# Banker_EDGE_2_SMA.net
KiCad netlist of a schematic drawn in Altium Designer
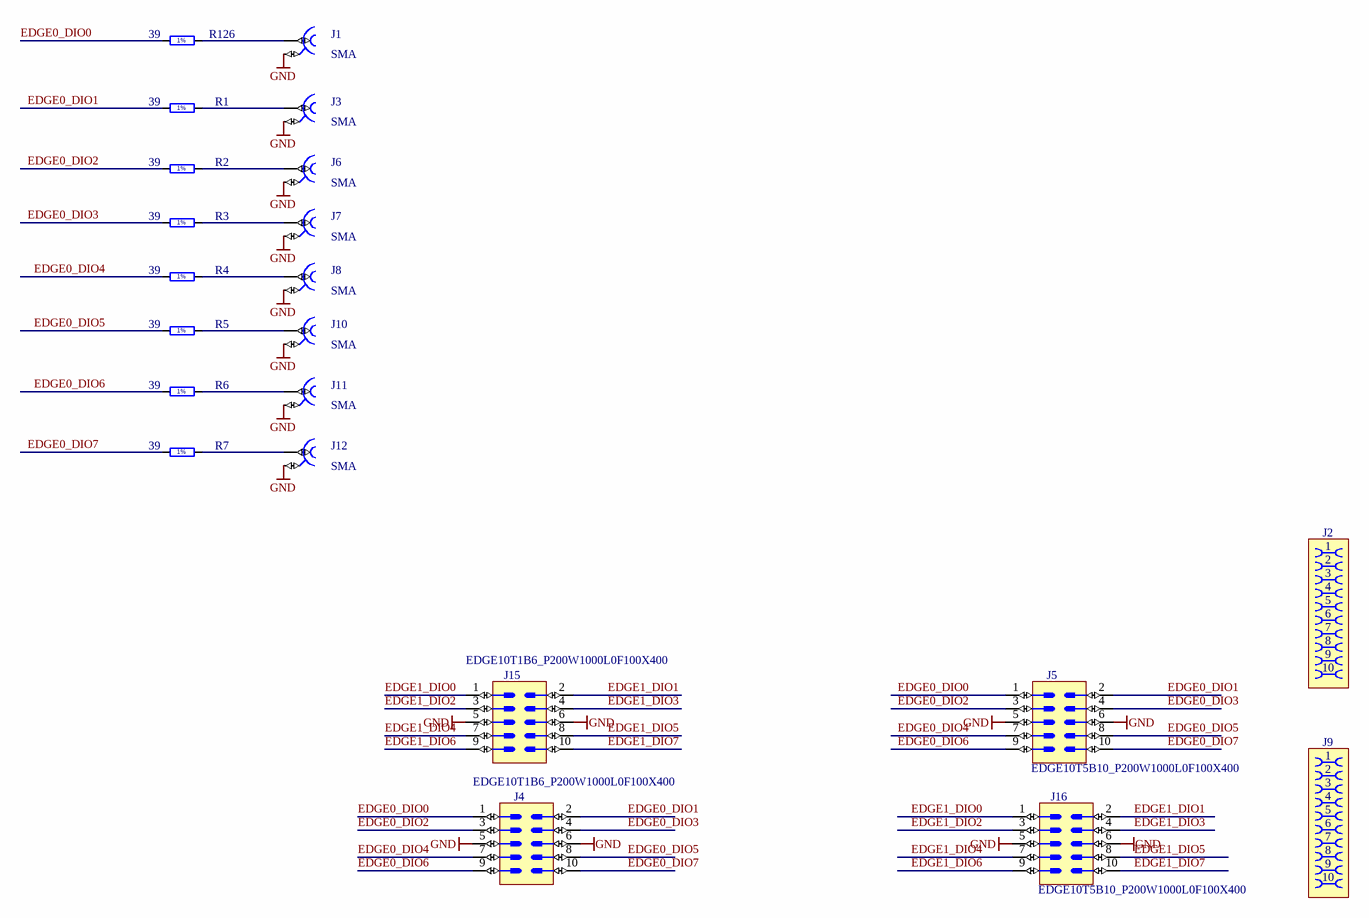
[diagram p0: Banker_EDGE_2_SMA.SchDoc]

(export (version "E")
  (design (tool "Eeschema 10.0.6"))
  (components
    (comp (ref "J1")
      (value "SMA")
      (footprint "Adam_TechRF2-19A-T-00-50-G")
      (description "SMA 50 Ohms Straight PCB Jack")
      (fields
        (field (name "PART NUMBER") "RF2-19A-T-00-50-G")
        (field (name "MANUFACTURER") "Adam Tech")
        (field (name "AUTHOR") "GK")
      )
      (libsource (lib "LIBRARY_SCH") (part "CON_SMA_V_AdamTech"))
    )
    (comp (ref "J2")
      (value "~")
      (footprint "AVX_00 9159 010 061 916")
      (description "Open Ended Card Edge Connector, 9159 Series")
      (fields
        (field (name "PART NUMBER") "AVX_00 9159 010 061 916")
        (field (name "MANUFACTURER") "AVX")
        (field (name "AUTHOR") "CERN DEM MR")
      )
      (libsource (lib "Connectors") (part "AVX_00 9159 010 061 916"))
    )
    (comp (ref "J3")
      (value "SMA")
      (footprint "Adam_TechRF2-19A-T-00-50-G")
      (description "SMA 50 Ohms Straight PCB Jack")
      (fields
        (field (name "PART NUMBER") "RF2-19A-T-00-50-G")
        (field (name "MANUFACTURER") "Adam Tech")
        (field (name "AUTHOR") "GK")
      )
      (libsource (lib "LIBRARY_SCH") (part "CON_SMA_V_AdamTech"))
    )
    (comp (ref "J4")
      (value "~")
      (footprint "EDGE10T1B6_P200W1000L0F100X400")
      (description "PCB Edge Connector 10 (2x5)")
      (fields
        (field (name "PART NUMBER") "EDGE10T1B6_P200W1000L0F100X400")
        (field (name "AUTHOR") "CERN DEM MR")
      )
      (libsource (lib "Connectors") (part "PCB Edge Connector 10 (2x5)"))
    )
    (comp (ref "J5")
      (value "~")
      (footprint "EDGE10T5B10_P200W1000L0F100X400")
      (description "PCB Edge Connector 10 (2x5)")
      (fields
        (field (name "PART NUMBER") "EDGE10T5B10_P200W1000L0F100X400")
        (field (name "AUTHOR") "CERN DEM MR")
      )
      (libsource (lib "Connectors") (part "PCB Edge Connector 10 (2x5)"))
    )
    (comp (ref "J6")
      (value "SMA")
      (footprint "Adam_TechRF2-19A-T-00-50-G")
      (description "SMA 50 Ohms Straight PCB Jack")
      (fields
        (field (name "PART NUMBER") "RF2-19A-T-00-50-G")
        (field (name "MANUFACTURER") "Adam Tech")
        (field (name "AUTHOR") "GK")
      )
      (libsource (lib "LIBRARY_SCH") (part "CON_SMA_V_AdamTech"))
    )
    (comp (ref "J7")
      (value "SMA")
      (footprint "Adam_TechRF2-19A-T-00-50-G")
      (description "SMA 50 Ohms Straight PCB Jack")
      (fields
        (field (name "PART NUMBER") "RF2-19A-T-00-50-G")
        (field (name "MANUFACTURER") "Adam Tech")
        (field (name "AUTHOR") "GK")
      )
      (libsource (lib "LIBRARY_SCH") (part "CON_SMA_V_AdamTech"))
    )
    (comp (ref "J8")
      (value "SMA")
      (footprint "Adam_TechRF2-19A-T-00-50-G")
      (description "SMA 50 Ohms Straight PCB Jack")
      (fields
        (field (name "PART NUMBER") "RF2-19A-T-00-50-G")
        (field (name "MANUFACTURER") "Adam Tech")
        (field (name "AUTHOR") "GK")
      )
      (libsource (lib "LIBRARY_SCH") (part "CON_SMA_V_AdamTech"))
    )
    (comp (ref "J9")
      (value "~")
      (footprint "AVX_00 9159 010 061 916")
      (description "Open Ended Card Edge Connector, 9159 Series")
      (fields
        (field (name "PART NUMBER") "AVX_00 9159 010 061 916")
        (field (name "MANUFACTURER") "AVX")
        (field (name "AUTHOR") "CERN DEM MR")
      )
      (libsource (lib "Connectors") (part "AVX_00 9159 010 061 916"))
    )
    (comp (ref "J10")
      (value "SMA")
      (footprint "Adam_TechRF2-19A-T-00-50-G")
      (description "SMA 50 Ohms Straight PCB Jack")
      (fields
        (field (name "PART NUMBER") "RF2-19A-T-00-50-G")
        (field (name "MANUFACTURER") "Adam Tech")
        (field (name "AUTHOR") "GK")
      )
      (libsource (lib "LIBRARY_SCH") (part "CON_SMA_V_AdamTech"))
    )
    (comp (ref "J11")
      (value "SMA")
      (footprint "Adam_TechRF2-19A-T-00-50-G")
      (description "SMA 50 Ohms Straight PCB Jack")
      (fields
        (field (name "PART NUMBER") "RF2-19A-T-00-50-G")
        (field (name "MANUFACTURER") "Adam Tech")
        (field (name "AUTHOR") "GK")
      )
      (libsource (lib "LIBRARY_SCH") (part "CON_SMA_V_AdamTech"))
    )
    (comp (ref "J12")
      (value "SMA")
      (footprint "Adam_TechRF2-19A-T-00-50-G")
      (description "SMA 50 Ohms Straight PCB Jack")
      (fields
        (field (name "PART NUMBER") "RF2-19A-T-00-50-G")
        (field (name "MANUFACTURER") "Adam Tech")
        (field (name "AUTHOR") "GK")
      )
      (libsource (lib "LIBRARY_SCH") (part "CON_SMA_V_AdamTech"))
    )
    (comp (ref "J15")
      (value "~")
      (footprint "EDGE10T1B6_P200W1000L0F100X400")
      (description "PCB Edge Connector 10 (2x5)")
      (fields
        (field (name "PART NUMBER") "EDGE10T1B6_P200W1000L0F100X400")
        (field (name "AUTHOR") "CERN DEM MR")
      )
      (libsource (lib "Connectors") (part "PCB Edge Connector 10 (2x5)"))
    )
    (comp (ref "J16")
      (value "~")
      (footprint "EDGE10T5B10_P200W1000L0F100X400")
      (description "PCB Edge Connector 10 (2x5)")
      (fields
        (field (name "PART NUMBER") "EDGE10T5B10_P200W1000L0F100X400")
        (field (name "AUTHOR") "CERN DEM MR")
      )
      (libsource (lib "Connectors") (part "PCB Edge Connector 10 (2x5)"))
    )
    (comp (ref "R1")
      (value "39")
      (footprint "RESC2012X60N")
      (description "Resistor - 1%")
      (fields
        (field (name "PART NUMBER") "R0805_39R_1%_0.125W_100PPM")
        (field (name "POWER") "0.125W")
        (field (name "AUTHOR") "CERN DEM JLC")
      )
      (libsource (lib "Resistors") (part "Resistor - 1%"))
    )
    (comp (ref "R2")
      (value "39")
      (footprint "RESC2012X60N")
      (description "Resistor - 1%")
      (fields
        (field (name "PART NUMBER") "R0805_39R_1%_0.125W_100PPM")
        (field (name "POWER") "0.125W")
        (field (name "AUTHOR") "CERN DEM JLC")
      )
      (libsource (lib "Resistors") (part "Resistor - 1%"))
    )
    (comp (ref "R3")
      (value "39")
      (footprint "RESC2012X60N")
      (description "Resistor - 1%")
      (fields
        (field (name "PART NUMBER") "R0805_39R_1%_0.125W_100PPM")
        (field (name "POWER") "0.125W")
        (field (name "AUTHOR") "CERN DEM JLC")
      )
      (libsource (lib "Resistors") (part "Resistor - 1%"))
    )
    (comp (ref "R4")
      (value "39")
      (footprint "RESC2012X60N")
      (description "Resistor - 1%")
      (fields
        (field (name "PART NUMBER") "R0805_39R_1%_0.125W_100PPM")
        (field (name "POWER") "0.125W")
        (field (name "AUTHOR") "CERN DEM JLC")
      )
      (libsource (lib "Resistors") (part "Resistor - 1%"))
    )
    (comp (ref "R5")
      (value "39")
      (footprint "RESC2012X60N")
      (description "Resistor - 1%")
      (fields
        (field (name "PART NUMBER") "R0805_39R_1%_0.125W_100PPM")
        (field (name "POWER") "0.125W")
        (field (name "AUTHOR") "CERN DEM JLC")
      )
      (libsource (lib "Resistors") (part "Resistor - 1%"))
    )
    (comp (ref "R6")
      (value "39")
      (footprint "RESC2012X60N")
      (description "Resistor - 1%")
      (fields
        (field (name "PART NUMBER") "R0805_39R_1%_0.125W_100PPM")
        (field (name "POWER") "0.125W")
        (field (name "AUTHOR") "CERN DEM JLC")
      )
      (libsource (lib "Resistors") (part "Resistor - 1%"))
    )
    (comp (ref "R7")
      (value "39")
      (footprint "RESC2012X60N")
      (description "Resistor - 1%")
      (fields
        (field (name "PART NUMBER") "R0805_39R_1%_0.125W_100PPM")
        (field (name "POWER") "0.125W")
        (field (name "AUTHOR") "CERN DEM JLC")
      )
      (libsource (lib "Resistors") (part "Resistor - 1%"))
    )
    (comp (ref "R126")
      (value "39")
      (footprint "RESC2012X60N")
      (description "Resistor - 1%")
      (fields
        (field (name "PART NUMBER") "R0805_39R_1%_0.125W_100PPM")
        (field (name "POWER") "0.125W")
        (field (name "AUTHOR") "CERN DEM JLC")
      )
      (libsource (lib "Resistors") (part "Resistor - 1%"))
    )
  )
  (nets
    (net (code "1") (name "/EDGE0_DIO0") (class "Default")
      (node (ref "J4") (pin "1") (pinfunction "1_1") (pintype "bidirectional"))
      (node (ref "J5") (pin "1") (pinfunction "1_1") (pintype "bidirectional"))
      (node (ref "R126") (pin "1") (pinfunction "1_1") (pintype "passive"))
    )
    (net (code "2") (name "/EDGE0_DIO1") (class "Default")
      (node (ref "J4") (pin "2") (pinfunction "2_2") (pintype "bidirectional"))
      (node (ref "J5") (pin "2") (pinfunction "2_2") (pintype "bidirectional"))
      (node (ref "R1") (pin "1") (pinfunction "1_1") (pintype "passive"))
    )
    (net (code "3") (name "/EDGE0_DIO2") (class "Default")
      (node (ref "J4") (pin "3") (pinfunction "3_3") (pintype "bidirectional"))
      (node (ref "J5") (pin "3") (pinfunction "3_3") (pintype "bidirectional"))
      (node (ref "R2") (pin "1") (pinfunction "1_1") (pintype "passive"))
    )
    (net (code "4") (name "/EDGE0_DIO3") (class "Default")
      (node (ref "J4") (pin "4") (pinfunction "4_4") (pintype "bidirectional"))
      (node (ref "J5") (pin "4") (pinfunction "4_4") (pintype "bidirectional"))
      (node (ref "R3") (pin "1") (pinfunction "1_1") (pintype "passive"))
    )
    (net (code "5") (name "/EDGE0_DIO4") (class "Default")
      (node (ref "J4") (pin "7") (pinfunction "7_7") (pintype "bidirectional"))
      (node (ref "J5") (pin "7") (pinfunction "7_7") (pintype "bidirectional"))
      (node (ref "R4") (pin "1") (pinfunction "1_1") (pintype "passive"))
    )
    (net (code "6") (name "/EDGE0_DIO5") (class "Default")
      (node (ref "J4") (pin "8") (pinfunction "8_8") (pintype "bidirectional"))
      (node (ref "J5") (pin "8") (pinfunction "8_8") (pintype "bidirectional"))
      (node (ref "R5") (pin "1") (pinfunction "1_1") (pintype "passive"))
    )
    (net (code "7") (name "/EDGE0_DIO6") (class "Default")
      (node (ref "J4") (pin "9") (pinfunction "9_9") (pintype "bidirectional"))
      (node (ref "J5") (pin "9") (pinfunction "9_9") (pintype "bidirectional"))
      (node (ref "R6") (pin "1") (pinfunction "1_1") (pintype "passive"))
    )
    (net (code "8") (name "/EDGE0_DIO7") (class "Default")
      (node (ref "J4") (pin "10") (pinfunction "10_10") (pintype "bidirectional"))
      (node (ref "J5") (pin "10") (pinfunction "10_10") (pintype "bidirectional"))
      (node (ref "R7") (pin "1") (pinfunction "1_1") (pintype "passive"))
    )
    (net (code "9") (name "/EDGE1_DIO0") (class "Default")
      (node (ref "J15") (pin "1") (pinfunction "1_1") (pintype "bidirectional"))
      (node (ref "J16") (pin "1") (pinfunction "1_1") (pintype "bidirectional"))
    )
    (net (code "10") (name "/EDGE1_DIO1") (class "Default")
      (node (ref "J15") (pin "2") (pinfunction "2_2") (pintype "bidirectional"))
      (node (ref "J16") (pin "2") (pinfunction "2_2") (pintype "bidirectional"))
    )
    (net (code "11") (name "/EDGE1_DIO2") (class "Default")
      (node (ref "J15") (pin "3") (pinfunction "3_3") (pintype "bidirectional"))
      (node (ref "J16") (pin "3") (pinfunction "3_3") (pintype "bidirectional"))
    )
    (net (code "12") (name "/EDGE1_DIO3") (class "Default")
      (node (ref "J15") (pin "4") (pinfunction "4_4") (pintype "bidirectional"))
      (node (ref "J16") (pin "4") (pinfunction "4_4") (pintype "bidirectional"))
    )
    (net (code "13") (name "/EDGE1_DIO4") (class "Default")
      (node (ref "J15") (pin "7") (pinfunction "7_7") (pintype "bidirectional"))
      (node (ref "J16") (pin "7") (pinfunction "7_7") (pintype "bidirectional"))
    )
    (net (code "14") (name "/EDGE1_DIO5") (class "Default")
      (node (ref "J15") (pin "8") (pinfunction "8_8") (pintype "bidirectional"))
      (node (ref "J16") (pin "8") (pinfunction "8_8") (pintype "bidirectional"))
    )
    (net (code "15") (name "/EDGE1_DIO6") (class "Default")
      (node (ref "J15") (pin "9") (pinfunction "9_9") (pintype "bidirectional"))
      (node (ref "J16") (pin "9") (pinfunction "9_9") (pintype "bidirectional"))
    )
    (net (code "16") (name "/EDGE1_DIO7") (class "Default")
      (node (ref "J15") (pin "10") (pinfunction "10_10") (pintype "bidirectional"))
      (node (ref "J16") (pin "10") (pinfunction "10_10") (pintype "bidirectional"))
    )
    (net (code "17") (name "GND") (class "Default")
      (node (ref "J1") (pin "2") (pinfunction "2_2") (pintype "bidirectional"))
      (node (ref "J10") (pin "2") (pinfunction "2_2") (pintype "bidirectional"))
      (node (ref "J11") (pin "2") (pinfunction "2_2") (pintype "bidirectional"))
      (node (ref "J12") (pin "2") (pinfunction "2_2") (pintype "bidirectional"))
      (node (ref "J15") (pin "5") (pinfunction "5_5") (pintype "bidirectional"))
      (node (ref "J15") (pin "6") (pinfunction "6_6") (pintype "bidirectional"))
      (node (ref "J16") (pin "5") (pinfunction "5_5") (pintype "bidirectional"))
      (node (ref "J16") (pin "6") (pinfunction "6_6") (pintype "bidirectional"))
      (node (ref "J3") (pin "2") (pinfunction "2_2") (pintype "bidirectional"))
      (node (ref "J4") (pin "5") (pinfunction "5_5") (pintype "bidirectional"))
      (node (ref "J4") (pin "6") (pinfunction "6_6") (pintype "bidirectional"))
      (node (ref "J5") (pin "5") (pinfunction "5_5") (pintype "bidirectional"))
      (node (ref "J5") (pin "6") (pinfunction "6_6") (pintype "bidirectional"))
      (node (ref "J6") (pin "2") (pinfunction "2_2") (pintype "bidirectional"))
      (node (ref "J7") (pin "2") (pinfunction "2_2") (pintype "bidirectional"))
      (node (ref "J8") (pin "2") (pinfunction "2_2") (pintype "bidirectional"))
    )
    (net (code "18") (name "Net-(J1-Pad1)") (class "Default")
      (node (ref "J1") (pin "1") (pinfunction "1_1") (pintype "bidirectional"))
      (node (ref "R126") (pin "2") (pinfunction "2_2") (pintype "passive"))
    )
    (net (code "19") (name "Net-(J3-Pad1)") (class "Default")
      (node (ref "J3") (pin "1") (pinfunction "1_1") (pintype "bidirectional"))
      (node (ref "R1") (pin "2") (pinfunction "2_2") (pintype "passive"))
    )
    (net (code "20") (name "Net-(J6-Pad1)") (class "Default")
      (node (ref "J6") (pin "1") (pinfunction "1_1") (pintype "bidirectional"))
      (node (ref "R2") (pin "2") (pinfunction "2_2") (pintype "passive"))
    )
    (net (code "21") (name "Net-(J7-Pad1)") (class "Default")
      (node (ref "J7") (pin "1") (pinfunction "1_1") (pintype "bidirectional"))
      (node (ref "R3") (pin "2") (pinfunction "2_2") (pintype "passive"))
    )
    (net (code "22") (name "Net-(J8-Pad1)") (class "Default")
      (node (ref "J8") (pin "1") (pinfunction "1_1") (pintype "bidirectional"))
      (node (ref "R4") (pin "2") (pinfunction "2_2") (pintype "passive"))
    )
    (net (code "23") (name "Net-(J10-Pad1)") (class "Default")
      (node (ref "J10") (pin "1") (pinfunction "1_1") (pintype "bidirectional"))
      (node (ref "R5") (pin "2") (pinfunction "2_2") (pintype "passive"))
    )
    (net (code "24") (name "Net-(J11-Pad1)") (class "Default")
      (node (ref "J11") (pin "1") (pinfunction "1_1") (pintype "bidirectional"))
      (node (ref "R6") (pin "2") (pinfunction "2_2") (pintype "passive"))
    )
    (net (code "25") (name "Net-(J12-Pad1)") (class "Default")
      (node (ref "J12") (pin "1") (pinfunction "1_1") (pintype "bidirectional"))
      (node (ref "R7") (pin "2") (pinfunction "2_2") (pintype "passive"))
    )
  )
)
